# ReDevelo_rev_A.net
KiCad netlist of a schematic drawn in EAGLE
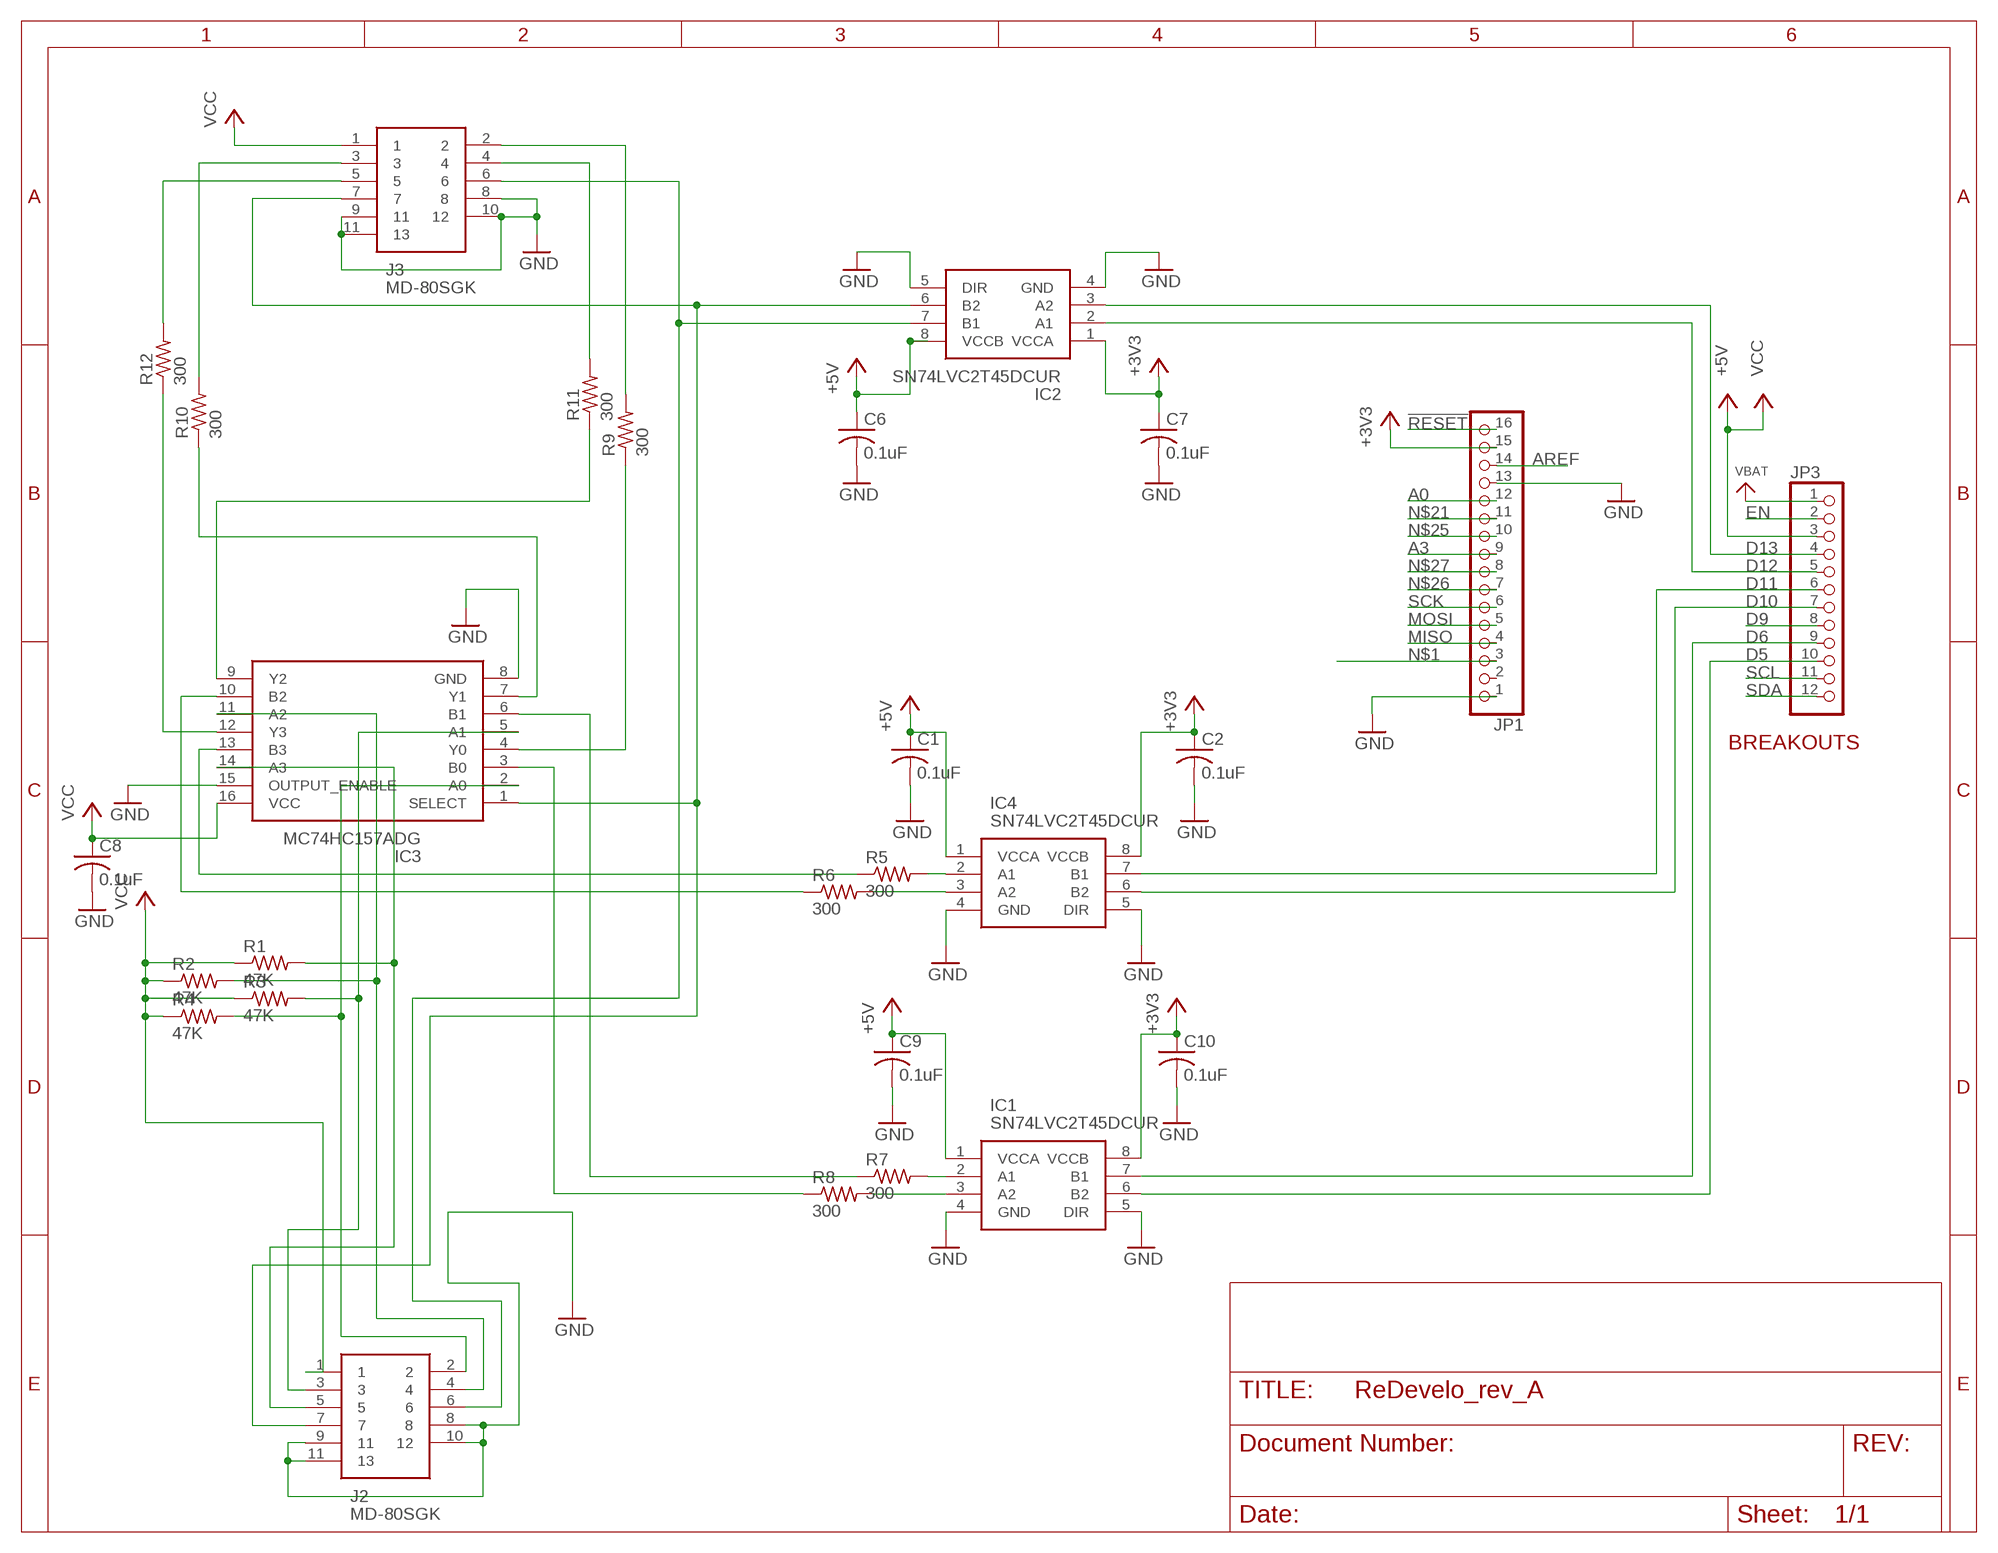
[diagram p0: schematic, sheet 1]

(export (version "E")
  (design (tool "Eeschema 10.0.6"))
  (components
    (comp (ref "C1")
      (value "0.1uF")
      (footprint "eagle-import:C0603")
      (libsource (lib "eagle-import") (part "C-USC0603"))
    )
    (comp (ref "C2")
      (value "0.1uF")
      (footprint "eagle-import:C0603")
      (libsource (lib "eagle-import") (part "C-USC0603"))
    )
    (comp (ref "C6")
      (value "0.1uF")
      (footprint "eagle-import:C0603")
      (libsource (lib "eagle-import") (part "C-USC0603"))
    )
    (comp (ref "C7")
      (value "0.1uF")
      (footprint "eagle-import:C0603")
      (libsource (lib "eagle-import") (part "C-USC0603"))
    )
    (comp (ref "C8")
      (value "0.1uF")
      (footprint "eagle-import:C0603")
      (libsource (lib "eagle-import") (part "C-USC0603"))
    )
    (comp (ref "C9")
      (value "0.1uF")
      (footprint "eagle-import:C0603")
      (libsource (lib "eagle-import") (part "C-USC0603"))
    )
    (comp (ref "C10")
      (value "0.1uF")
      (footprint "eagle-import:C0603")
      (libsource (lib "eagle-import") (part "C-USC0603"))
    )
    (comp (ref "IC1")
      (value "SN74LVC2T45DCUR")
      (footprint "eagle-import:SOP50P310X90-8N")
      (fields (field (name "MOUSER_PART_NUMBER") "595-SN74LVC2T45DCUR"))
      (libsource (lib "eagle-import") (part "SN74LVC2T45DCUR"))
    )
    (comp (ref "IC2")
      (value "SN74LVC2T45DCUR")
      (footprint "eagle-import:SOP50P310X90-8N")
      (fields (field (name "MOUSER_PART_NUMBER") "595-SN74LVC2T45DCUR"))
      (libsource (lib "eagle-import") (part "SN74LVC2T45DCUR"))
    )
    (comp (ref "IC3")
      (value "MC74HC157ADG")
      (footprint "eagle-import:SOIC127P600X175-16N")
      (fields
        (field (name "MOUSER_PART_NUMBER") "863-MC74HC157ADG")
        (field (name "RS_PART_NUMBER") "8061422P")
      )
      (libsource (lib "eagle-import") (part "MC74HC157ADG"))
    )
    (comp (ref "IC4")
      (value "SN74LVC2T45DCUR")
      (footprint "eagle-import:SOP50P310X90-8N")
      (fields (field (name "MOUSER_PART_NUMBER") "595-SN74LVC2T45DCUR"))
      (libsource (lib "eagle-import") (part "SN74LVC2T45DCUR"))
    )
    (comp (ref "J2")
      (value "MD-80SGK")
      (footprint "eagle-import:MD80SGK")
      (fields (field (name "MOUSER_PART_NUMBER") "490-MD-80SGK"))
      (libsource (lib "eagle-import") (part "MD-80SGK"))
    )
    (comp (ref "J3")
      (value "MD-80SGK")
      (footprint "eagle-import:MD80SGK")
      (fields (field (name "MOUSER_PART_NUMBER") "490-MD-80SGK"))
      (libsource (lib "eagle-import") (part "MD-80SGK"))
    )
    (comp (ref "JP1")
      (value "HEADER-1X16ROUND")
      (footprint "eagle-import:1X16_ROUND")
      (libsource (lib "eagle-import") (part "HEADER-1X16ROUND"))
    )
    (comp (ref "JP3")
      (value "HEADER-1X12")
      (footprint "eagle-import:1X12_ROUND")
      (libsource (lib "eagle-import") (part "HEADER-1X12"))
    )
    (comp (ref "R1")
      (value "47K")
      (footprint "eagle-import:R0603")
      (libsource (lib "eagle-import") (part "R-US_R0603"))
    )
    (comp (ref "R2")
      (value "47K")
      (footprint "eagle-import:R0603")
      (libsource (lib "eagle-import") (part "R-US_R0603"))
    )
    (comp (ref "R3")
      (value "47K")
      (footprint "eagle-import:R0603")
      (libsource (lib "eagle-import") (part "R-US_R0603"))
    )
    (comp (ref "R4")
      (value "47K")
      (footprint "eagle-import:R0603")
      (libsource (lib "eagle-import") (part "R-US_R0603"))
    )
    (comp (ref "R5")
      (value "300")
      (footprint "eagle-import:R0603")
      (libsource (lib "eagle-import") (part "R-US_R0603"))
    )
    (comp (ref "R6")
      (value "300")
      (footprint "eagle-import:R0603")
      (libsource (lib "eagle-import") (part "R-US_R0603"))
    )
    (comp (ref "R7")
      (value "300")
      (footprint "eagle-import:R0603")
      (libsource (lib "eagle-import") (part "R-US_R0603"))
    )
    (comp (ref "R8")
      (value "300")
      (footprint "eagle-import:R0603")
      (libsource (lib "eagle-import") (part "R-US_R0603"))
    )
    (comp (ref "R9")
      (value "300")
      (footprint "eagle-import:R0603")
      (libsource (lib "eagle-import") (part "R-US_R0603"))
    )
    (comp (ref "R10")
      (value "300")
      (footprint "eagle-import:R0603")
      (libsource (lib "eagle-import") (part "R-US_R0603"))
    )
    (comp (ref "R11")
      (value "300")
      (footprint "eagle-import:R0603")
      (libsource (lib "eagle-import") (part "R-US_R0603"))
    )
    (comp (ref "R12")
      (value "300")
      (footprint "eagle-import:R0603")
      (libsource (lib "eagle-import") (part "R-US_R0603"))
    )
  )
  (nets
    (net (code "1") (name "+3V3") (class "Default")
      (node (ref "C10") (pin "1") (pinfunction "1_1") (pintype "passive"))
      (node (ref "C2") (pin "1") (pinfunction "1_1") (pintype "passive"))
      (node (ref "C7") (pin "1") (pinfunction "1_1") (pintype "passive"))
      (node (ref "IC1") (pin "8") (pinfunction "VCCB_8") (pintype "bidirectional"))
      (node (ref "IC2") (pin "1") (pinfunction "VCCA_1") (pintype "bidirectional"))
      (node (ref "IC4") (pin "8") (pinfunction "VCCB_8") (pintype "bidirectional"))
      (node (ref "JP1") (pin "15") (pinfunction "15_15") (pintype "passive"))
    )
    (net (code "2") (name "+5V") (class "Default")
      (node (ref "C1") (pin "1") (pinfunction "1_1") (pintype "passive"))
      (node (ref "C6") (pin "1") (pinfunction "1_1") (pintype "passive"))
      (node (ref "C8") (pin "1") (pinfunction "1_1") (pintype "passive"))
      (node (ref "C9") (pin "1") (pinfunction "1_1") (pintype "passive"))
      (node (ref "IC1") (pin "1") (pinfunction "VCCA_1") (pintype "bidirectional"))
      (node (ref "IC2") (pin "8") (pinfunction "VCCB_8") (pintype "bidirectional"))
      (node (ref "IC3") (pin "16") (pinfunction "VCC_16") (pintype "power_in"))
      (node (ref "IC4") (pin "1") (pinfunction "VCCA_1") (pintype "bidirectional"))
      (node (ref "J2") (pin "1") (pinfunction "1_1") (pintype "bidirectional"))
      (node (ref "J3") (pin "1") (pinfunction "1_1") (pintype "bidirectional"))
      (node (ref "JP3") (pin "3") (pinfunction "3_3") (pintype "passive"))
      (node (ref "R1") (pin "1") (pinfunction "1_1") (pintype "passive"))
      (node (ref "R2") (pin "1") (pinfunction "1_1") (pintype "passive"))
      (node (ref "R3") (pin "1") (pinfunction "1_1") (pintype "passive"))
      (node (ref "R4") (pin "1") (pinfunction "1_1") (pintype "passive"))
    )
    (net (code "3") (name "/A0") (class "Default")
      (node (ref "JP1") (pin "12") (pinfunction "12_12") (pintype "passive"))
    )
    (net (code "4") (name "/A3") (class "Default")
      (node (ref "JP1") (pin "9") (pinfunction "9_9") (pintype "passive"))
    )
    (net (code "5") (name "/AREF") (class "Default")
      (node (ref "JP1") (pin "14") (pinfunction "14_14") (pintype "passive"))
    )
    (net (code "6") (name "/D5") (class "Default")
      (node (ref "IC1") (pin "6") (pinfunction "B2_6") (pintype "bidirectional"))
      (node (ref "JP3") (pin "10") (pinfunction "10_10") (pintype "passive"))
    )
    (net (code "7") (name "/D6") (class "Default")
      (node (ref "IC1") (pin "7") (pinfunction "B1_7") (pintype "bidirectional"))
      (node (ref "JP3") (pin "9") (pinfunction "9_9") (pintype "passive"))
    )
    (net (code "8") (name "/D9") (class "Default")
      (node (ref "JP3") (pin "8") (pinfunction "8_8") (pintype "passive"))
    )
    (net (code "9") (name "/D10") (class "Default")
      (node (ref "IC4") (pin "6") (pinfunction "B2_6") (pintype "bidirectional"))
      (node (ref "JP3") (pin "7") (pinfunction "7_7") (pintype "passive"))
    )
    (net (code "10") (name "/D11") (class "Default")
      (node (ref "IC4") (pin "7") (pinfunction "B1_7") (pintype "bidirectional"))
      (node (ref "JP3") (pin "6") (pinfunction "6_6") (pintype "passive"))
    )
    (net (code "11") (name "/D12") (class "Default")
      (node (ref "IC2") (pin "2") (pinfunction "A1_2") (pintype "bidirectional"))
      (node (ref "JP3") (pin "5") (pinfunction "5_5") (pintype "passive"))
    )
    (net (code "12") (name "/D13") (class "Default")
      (node (ref "IC2") (pin "3") (pinfunction "A2_3") (pintype "bidirectional"))
      (node (ref "JP3") (pin "4") (pinfunction "4_4") (pintype "passive"))
    )
    (net (code "13") (name "/EN") (class "Default")
      (node (ref "JP3") (pin "2") (pinfunction "2_2") (pintype "passive"))
    )
    (net (code "14") (name "/MISO") (class "Default")
      (node (ref "JP1") (pin "4") (pinfunction "4_4") (pintype "passive"))
    )
    (net (code "15") (name "/MOSI") (class "Default")
      (node (ref "JP1") (pin "5") (pinfunction "5_5") (pintype "passive"))
    )
    (net (code "16") (name "/N$1") (class "Default")
      (node (ref "JP1") (pin "3") (pinfunction "3_3") (pintype "passive"))
    )
    (net (code "17") (name "/N$21") (class "Default")
      (node (ref "JP1") (pin "11") (pinfunction "11_11") (pintype "passive"))
    )
    (net (code "18") (name "/N$25") (class "Default")
      (node (ref "JP1") (pin "10") (pinfunction "10_10") (pintype "passive"))
    )
    (net (code "19") (name "/N$26") (class "Default")
      (node (ref "JP1") (pin "7") (pinfunction "7_7") (pintype "passive"))
    )
    (net (code "20") (name "/N$27") (class "Default")
      (node (ref "JP1") (pin "8") (pinfunction "8_8") (pintype "passive"))
    )
    (net (code "21") (name "/SCK") (class "Default")
      (node (ref "JP1") (pin "6") (pinfunction "6_6") (pintype "passive"))
    )
    (net (code "22") (name "/SCL") (class "Default")
      (node (ref "JP3") (pin "11") (pinfunction "11_11") (pintype "passive"))
    )
    (net (code "23") (name "/SDA") (class "Default")
      (node (ref "JP3") (pin "12") (pinfunction "12_12") (pintype "passive"))
    )
    (net (code "24") (name "/~{RESET}") (class "Default")
      (node (ref "JP1") (pin "16") (pinfunction "16_16") (pintype "passive"))
    )
    (net (code "25") (name "GND") (class "Default")
      (node (ref "C1") (pin "2") (pinfunction "2_2") (pintype "passive"))
      (node (ref "C10") (pin "2") (pinfunction "2_2") (pintype "passive"))
      (node (ref "C2") (pin "2") (pinfunction "2_2") (pintype "passive"))
      (node (ref "C6") (pin "2") (pinfunction "2_2") (pintype "passive"))
      (node (ref "C7") (pin "2") (pinfunction "2_2") (pintype "passive"))
      (node (ref "C8") (pin "2") (pinfunction "2_2") (pintype "passive"))
      (node (ref "C9") (pin "2") (pinfunction "2_2") (pintype "passive"))
      (node (ref "IC1") (pin "4") (pinfunction "GND_4") (pintype "bidirectional"))
      (node (ref "IC1") (pin "5") (pinfunction "DIR_5") (pintype "bidirectional"))
      (node (ref "IC2") (pin "4") (pinfunction "GND_4") (pintype "bidirectional"))
      (node (ref "IC2") (pin "5") (pinfunction "DIR_5") (pintype "bidirectional"))
      (node (ref "IC3") (pin "15") (pinfunction "OUTPUT_ENABLE_15") (pintype "input"))
      (node (ref "IC3") (pin "8") (pinfunction "GND_8") (pintype "power_in"))
      (node (ref "IC4") (pin "4") (pinfunction "GND_4") (pintype "bidirectional"))
      (node (ref "IC4") (pin "5") (pinfunction "DIR_5") (pintype "bidirectional"))
      (node (ref "J2") (pin "10") (pinfunction "12_10") (pintype "bidirectional"))
      (node (ref "J2") (pin "11") (pinfunction "13_11") (pintype "bidirectional"))
      (node (ref "J2") (pin "8") (pinfunction "8_8") (pintype "bidirectional"))
      (node (ref "J2") (pin "9") (pinfunction "11_9") (pintype "bidirectional"))
      (node (ref "J3") (pin "10") (pinfunction "12_10") (pintype "bidirectional"))
      (node (ref "J3") (pin "11") (pinfunction "13_11") (pintype "bidirectional"))
      (node (ref "J3") (pin "8") (pinfunction "8_8") (pintype "bidirectional"))
      (node (ref "J3") (pin "9") (pinfunction "11_9") (pintype "bidirectional"))
      (node (ref "JP1") (pin "1") (pinfunction "1_1") (pintype "passive"))
      (node (ref "JP1") (pin "13") (pinfunction "13_13") (pintype "passive"))
    )
    (net (code "26") (name "Net-(IC1-A1)") (class "Default")
      (node (ref "IC1") (pin "2") (pinfunction "A1_2") (pintype "bidirectional"))
      (node (ref "R7") (pin "2") (pinfunction "2_2") (pintype "passive"))
    )
    (net (code "27") (name "Net-(IC1-A2)") (class "Default")
      (node (ref "IC1") (pin "3") (pinfunction "A2_3") (pintype "bidirectional"))
      (node (ref "R8") (pin "2") (pinfunction "2_2") (pintype "passive"))
    )
    (net (code "28") (name "Net-(IC2-B1)") (class "Default")
      (node (ref "IC2") (pin "7") (pinfunction "B1_7") (pintype "bidirectional"))
      (node (ref "J2") (pin "6") (pinfunction "6_6") (pintype "bidirectional"))
      (node (ref "J3") (pin "6") (pinfunction "6_6") (pintype "bidirectional"))
    )
    (net (code "29") (name "Net-(IC2-B2)") (class "Default")
      (node (ref "IC2") (pin "6") (pinfunction "B2_6") (pintype "bidirectional"))
      (node (ref "IC3") (pin "1") (pinfunction "SELECT_1") (pintype "input"))
      (node (ref "J2") (pin "7") (pinfunction "7_7") (pintype "bidirectional"))
      (node (ref "J3") (pin "7") (pinfunction "7_7") (pintype "bidirectional"))
    )
    (net (code "30") (name "Net-(IC3-A0)") (class "Default")
      (node (ref "IC3") (pin "2") (pinfunction "A0_2") (pintype "input"))
      (node (ref "J2") (pin "2") (pinfunction "2_2") (pintype "bidirectional"))
      (node (ref "R4") (pin "2") (pinfunction "2_2") (pintype "passive"))
    )
    (net (code "31") (name "Net-(IC3-A1)") (class "Default")
      (node (ref "IC3") (pin "5") (pinfunction "A1_5") (pintype "input"))
      (node (ref "J2") (pin "3") (pinfunction "3_3") (pintype "bidirectional"))
      (node (ref "R3") (pin "2") (pinfunction "2_2") (pintype "passive"))
    )
    (net (code "32") (name "Net-(IC3-A2)") (class "Default")
      (node (ref "IC3") (pin "11") (pinfunction "A2_11") (pintype "input"))
      (node (ref "J2") (pin "4") (pinfunction "4_4") (pintype "bidirectional"))
      (node (ref "R2") (pin "2") (pinfunction "2_2") (pintype "passive"))
    )
    (net (code "33") (name "Net-(IC3-A3)") (class "Default")
      (node (ref "IC3") (pin "14") (pinfunction "A3_14") (pintype "input"))
      (node (ref "J2") (pin "5") (pinfunction "5_5") (pintype "bidirectional"))
      (node (ref "R1") (pin "2") (pinfunction "2_2") (pintype "passive"))
    )
    (net (code "34") (name "Net-(IC3-B0)") (class "Default")
      (node (ref "IC3") (pin "3") (pinfunction "B0_3") (pintype "input"))
      (node (ref "R8") (pin "1") (pinfunction "1_1") (pintype "passive"))
    )
    (net (code "35") (name "Net-(IC3-B1)") (class "Default")
      (node (ref "IC3") (pin "6") (pinfunction "B1_6") (pintype "input"))
      (node (ref "R7") (pin "1") (pinfunction "1_1") (pintype "passive"))
    )
    (net (code "36") (name "Net-(IC3-B2)") (class "Default")
      (node (ref "IC3") (pin "10") (pinfunction "B2_10") (pintype "input"))
      (node (ref "R6") (pin "1") (pinfunction "1_1") (pintype "passive"))
    )
    (net (code "37") (name "Net-(IC3-B3)") (class "Default")
      (node (ref "IC3") (pin "13") (pinfunction "B3_13") (pintype "input"))
      (node (ref "R5") (pin "1") (pinfunction "1_1") (pintype "passive"))
    )
    (net (code "38") (name "Net-(IC3-Y0)") (class "Default")
      (node (ref "IC3") (pin "4") (pinfunction "Y0_4") (pintype "output"))
      (node (ref "R9") (pin "1") (pinfunction "1_1") (pintype "passive"))
    )
    (net (code "39") (name "Net-(IC3-Y1)") (class "Default")
      (node (ref "IC3") (pin "7") (pinfunction "Y1_7") (pintype "output"))
      (node (ref "R10") (pin "1") (pinfunction "1_1") (pintype "passive"))
    )
    (net (code "40") (name "Net-(IC3-Y2)") (class "Default")
      (node (ref "IC3") (pin "9") (pinfunction "Y2_9") (pintype "output"))
      (node (ref "R11") (pin "1") (pinfunction "1_1") (pintype "passive"))
    )
    (net (code "41") (name "Net-(IC3-Y3)") (class "Default")
      (node (ref "IC3") (pin "12") (pinfunction "Y3_12") (pintype "output"))
      (node (ref "R12") (pin "1") (pinfunction "1_1") (pintype "passive"))
    )
    (net (code "42") (name "Net-(IC4-A1)") (class "Default")
      (node (ref "IC4") (pin "2") (pinfunction "A1_2") (pintype "bidirectional"))
      (node (ref "R5") (pin "2") (pinfunction "2_2") (pintype "passive"))
    )
    (net (code "43") (name "Net-(IC4-A2)") (class "Default")
      (node (ref "IC4") (pin "3") (pinfunction "A2_3") (pintype "bidirectional"))
      (node (ref "R6") (pin "2") (pinfunction "2_2") (pintype "passive"))
    )
    (net (code "44") (name "Net-(J3-Pad2)") (class "Default")
      (node (ref "J3") (pin "2") (pinfunction "2_2") (pintype "bidirectional"))
      (node (ref "R9") (pin "2") (pinfunction "2_2") (pintype "passive"))
    )
    (net (code "45") (name "Net-(J3-Pad3)") (class "Default")
      (node (ref "J3") (pin "3") (pinfunction "3_3") (pintype "bidirectional"))
      (node (ref "R10") (pin "2") (pinfunction "2_2") (pintype "passive"))
    )
    (net (code "46") (name "Net-(J3-Pad4)") (class "Default")
      (node (ref "J3") (pin "4") (pinfunction "4_4") (pintype "bidirectional"))
      (node (ref "R11") (pin "2") (pinfunction "2_2") (pintype "passive"))
    )
    (net (code "47") (name "Net-(J3-Pad5)") (class "Default")
      (node (ref "J3") (pin "5") (pinfunction "5_5") (pintype "bidirectional"))
      (node (ref "R12") (pin "2") (pinfunction "2_2") (pintype "passive"))
    )
    (net (code "48") (name "VBAT") (class "Default")
      (node (ref "JP3") (pin "1") (pinfunction "1_1") (pintype "passive"))
    )
    (net (code "49") (name "unconnected-(JP1-Pad2)") (class "Default")
      (node (ref "JP1") (pin "2") (pinfunction "2_2") (pintype "passive"))
    )
  )
)
